# Schematic.net
KiCad netlist of a schematic drawn in Altium Designer
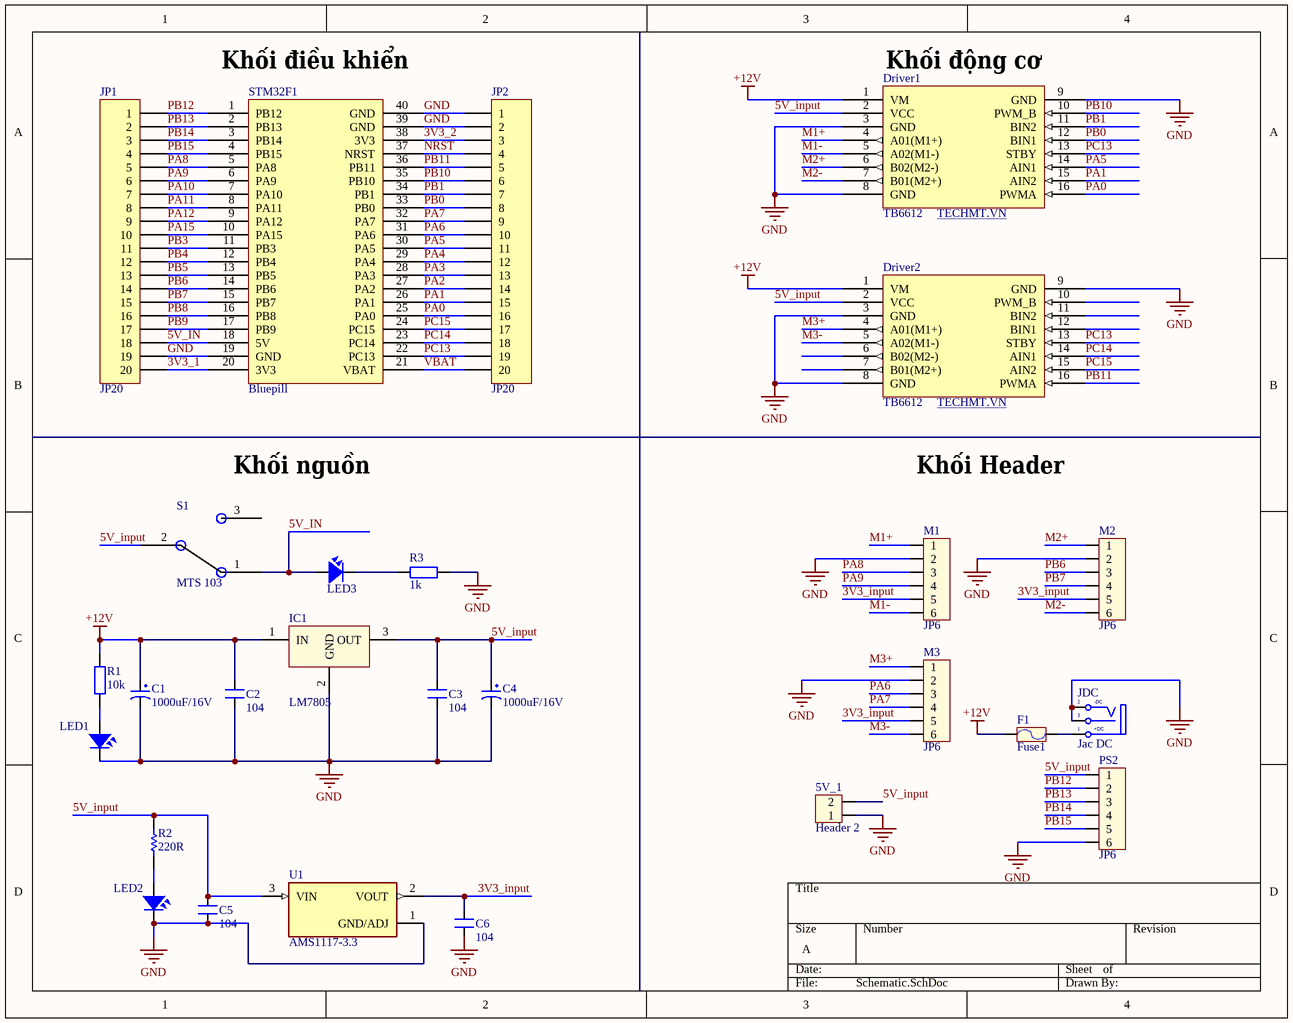
[diagram p0: Schematic.SchDoc]

(export (version "E")
  (design (tool "Eeschema 10.0.6"))
  (components
    (comp (ref "5V_1")
      (value "Header 2")
      (footprint "HED2")
      (description "Header 2 (Green)")
      (libsource (lib "echipkool-com-library") (part "Hed2"))
    )
    (comp (ref "C1")
      (value "1000uF/16V")
      (footprint "CP1.5/3.4")
      (description "Cap 100uF/35V - 470uF/16V")
      (libsource (lib "echipkool-com-library") (part "CP3"))
    )
    (comp (ref "C2")
      (value "104")
      (footprint "CN2")
      (description "Cap np 104 => 105pF")
      (libsource (lib "syhaunguyen") (part "CN2"))
    )
    (comp (ref "C3")
      (value "104")
      (footprint "CN2")
      (description "Cap np 104 => 105pF")
      (libsource (lib "syhaunguyen") (part "CN2"))
    )
    (comp (ref "C4")
      (value "1000uF/16V")
      (footprint "CP1.5/3.4")
      (description "Cap 100uF/35V - 470uF/16V")
      (libsource (lib "echipkool-com-library") (part "CP3"))
    )
    (comp (ref "C5")
      (value "104")
      (footprint "CN2")
      (description "Cap np 104 => 105pF")
      (libsource (lib "syhaunguyen") (part "CN2"))
    )
    (comp (ref "C6")
      (value "104")
      (footprint "CN2")
      (description "Cap np 104 => 105pF")
      (libsource (lib "echipkool-com-library") (part "CN2"))
    )
    (comp (ref "Driver1")
      (value "TB6612")
      (footprint "TB6612")
      (fields (field (name "WEB") "TECHMT.VN"))
      (libsource (lib "TechMT.VN_Lib_Project v2") (part "TB6612"))
    )
    (comp (ref "Driver2")
      (value "TB6612")
      (footprint "TB6612")
      (fields (field (name "WEB") "TECHMT.VN"))
      (libsource (lib "TechMT.VN_Lib_Project v2") (part "TB6612"))
    )
    (comp (ref "F1")
      (value "Fuse1")
      (footprint "Fuse1")
      (description "Fuse")
      (fields (field (name "DESIGNED BY") "VanDungEvn"))
      (libsource (lib "LIBRARYALT") (part "Fuse"))
    )
    (comp (ref "IC1")
      (value "LM7805")
      (footprint "QTO-220")
      (description "On ap +, from + 5 to + 24VDC")
      (libsource (lib "echipkool-com-library") (part "LM78xx"))
    )
    (comp (ref "JDC")
      (value "Jac DC")
      (footprint "DC-IN")
      (description "Jac DC input")
      (libsource (lib "syhaunguyen") (part "DCIN"))
    )
    (comp (ref "JP1")
      (value "JP20")
      (footprint "JP20-D1T")
      (description "WR-PHD 2.54 mm Angled Socket Header")
      (fields
        (field (name "MANUFACTURER") "Würth Elektronik eiSos GmbH")
        (field (name "PARTNO") "613020143121")
        (field (name "CREATED BY") "Karrer Zheng")
      )
      (libsource (lib "TechMT.VN_Lib_Project v2") (part "JP20"))
    )
    (comp (ref "JP2")
      (value "JP20")
      (footprint "JP20-D1T")
      (description "WR-PHD 2.54 mm Angled Socket Header")
      (fields
        (field (name "MANUFACTURER") "Würth Elektronik eiSos GmbH")
        (field (name "PARTNO") "613020143121")
        (field (name "CREATED BY") "Karrer Zheng")
      )
      (libsource (lib "") (part "JP20_1"))
    )
    (comp (ref "LED1")
      (value "LED")
      (footprint "LED-3")
      (description "LED Single colour Green and Red")
      (libsource (lib "echipkool-com-library") (part "LED"))
    )
    (comp (ref "LED2")
      (value "LED")
      (footprint "LED-3")
      (description "LED Single colour Green and Red")
      (libsource (lib "echipkool-com-library") (part "LED"))
    )
    (comp (ref "LED3")
      (value "LED")
      (footprint "LED-3")
      (description "LED Single colour Green and Red")
      (libsource (lib "echipkool-com-library") (part "LED"))
    )
    (comp (ref "M1")
      (value "JP6")
      (footprint "CON_6P")
      (description "Connector 6")
      (libsource (lib "My Library") (part "Con6"))
    )
    (comp (ref "M2")
      (value "JP6")
      (footprint "CON_6P")
      (description "Connector 6")
      (libsource (lib "echipkool-com-library") (part "Con6"))
    )
    (comp (ref "M3")
      (value "JP6")
      (footprint "CON_6P")
      (description "Connector 6")
      (libsource (lib "echipkool-com-library") (part "Con6"))
    )
    (comp (ref "PS2")
      (value "JP6")
      (footprint "CON_6P")
      (description "Connector 6")
      (libsource (lib "echipkool-com-library") (part "Con6"))
    )
    (comp (ref "R1")
      (value "10k")
      (footprint "R1/4W")
      (description "Resistor 1/4W")
      (libsource (lib "echipkool-com-library") (part "R1/4W"))
    )
    (comp (ref "R2")
      (value "220R")
      (footprint "R1/4W")
      (description "Resistor")
      (fields
        (field (name "MANUFACTURER") "Generic Components")
        (field (name "Comment") "Res1")
        (field (name "PUBLISHER") "Altium Hobart Technology Centre")
      )
      (libsource (lib "echipkool-com-library") (part "Res1_4"))
    )
    (comp (ref "R3")
      (value "1k")
      (footprint "R1/4W")
      (description "Resistor 1/4W")
      (libsource (lib "echipkool-com-library") (part "R1/4W"))
    )
    (comp (ref "S1") (value "MTS 103") (footprint "MTS 103") (libsource (lib "MTS103") (part "MTS 103")))
    (comp (ref "STM32F1")
      (value "Bluepill")
      (footprint "Blue Pill")
      (description "STM32F103C8T6")
      (libsource (lib "Bluepill") (part "STM32F103C8T6"))
    )
    (comp (ref "U1")
      (value "AMS1117-3.3")
      (footprint "SOT229P700X180-4N")
      (description "Sot223/Pkg 1-Amp 3.3-Volt Low Drop Out Voltage Regulatator")
      (fields (field (name "MF") "Advanced Monolithic Systems"))
      (libsource (lib "AMS1117-3.3") (part "AMS1117-3.3"))
    )
  )
  (nets
    (net (code "1") (name "+12V") (class "Default")
      (node (ref "C1") (pin "1") (pinfunction "1_1") (pintype "passive"))
      (node (ref "C2") (pin "2") (pinfunction "2_2") (pintype "passive"))
      (node (ref "Driver1") (pin "1") (pinfunction "VM_1") (pintype "power_in"))
      (node (ref "Driver2") (pin "1") (pinfunction "VM_1") (pintype "power_in"))
      (node (ref "F1") (pin "1") (pinfunction "1_1") (pintype "passive"))
      (node (ref "IC1") (pin "1") (pinfunction "IN_1") (pintype "passive"))
      (node (ref "R1") (pin "2") (pinfunction "2_2") (pintype "passive"))
    )
    (net (code "2") (name "/3V3_1") (class "Default")
      (node (ref "JP1") (pin "20") (pinfunction "20_20") (pintype "passive"))
      (node (ref "STM32F1") (pin "20") (pinfunction "3V3_20") (pintype "passive"))
    )
    (net (code "3") (name "/3V3_2") (class "Default")
      (node (ref "JP2") (pin "3") (pinfunction "3_3") (pintype "passive"))
      (node (ref "STM32F1") (pin "38") (pinfunction "3V3_38") (pintype "passive"))
    )
    (net (code "4") (name "/3V3_input") (class "Default")
      (node (ref "C6") (pin "2") (pinfunction "2_2") (pintype "passive"))
      (node (ref "M1") (pin "5") (pinfunction "5_5") (pintype "passive"))
      (node (ref "M2") (pin "5") (pinfunction "5_5") (pintype "passive"))
      (node (ref "M3") (pin "5") (pinfunction "5_5") (pintype "passive"))
      (node (ref "U1") (pin "2") (pinfunction "VOUT_2") (pintype "output"))
    )
    (net (code "5") (name "/5V_IN") (class "Default")
      (node (ref "JP1") (pin "18") (pinfunction "18_18") (pintype "passive"))
      (node (ref "LED3") (pin "1") (pinfunction "1_1") (pintype "passive"))
      (node (ref "S1") (pin "1") (pinfunction "1_1") (pintype "passive"))
      (node (ref "STM32F1") (pin "18") (pinfunction "5V_18") (pintype "passive"))
    )
    (net (code "6") (name "/5V_input") (class "Default")
      (node (ref "5V_1") (pin "2") (pinfunction "2_2") (pintype "passive"))
      (node (ref "C3") (pin "2") (pinfunction "2_2") (pintype "passive"))
      (node (ref "C4") (pin "1") (pinfunction "1_1") (pintype "passive"))
      (node (ref "C5") (pin "2") (pinfunction "2_2") (pintype "passive"))
      (node (ref "Driver1") (pin "2") (pinfunction "VCC_2") (pintype "power_in"))
      (node (ref "Driver2") (pin "2") (pinfunction "VCC_2") (pintype "power_in"))
      (node (ref "IC1") (pin "3") (pinfunction "OUT_3") (pintype "passive"))
      (node (ref "PS2") (pin "1") (pinfunction "1_1") (pintype "passive"))
      (node (ref "R2") (pin "2") (pinfunction "2_2") (pintype "passive"))
      (node (ref "S1") (pin "2") (pinfunction "4_2") (pintype "passive"))
      (node (ref "U1") (pin "3") (pinfunction "VIN_3") (pintype "input"))
    )
    (net (code "7") (name "/M1+") (class "Default")
      (node (ref "Driver1") (pin "4") (pinfunction "A01(M1+)_4") (pintype "output"))
      (node (ref "M1") (pin "1") (pinfunction "1_1") (pintype "passive"))
    )
    (net (code "8") (name "/M1-") (class "Default")
      (node (ref "Driver1") (pin "5") (pinfunction "A02(M1-)_5") (pintype "output"))
      (node (ref "M1") (pin "6") (pinfunction "6_6") (pintype "passive"))
    )
    (net (code "9") (name "/M2+") (class "Default")
      (node (ref "Driver1") (pin "6") (pinfunction "B02(M2-)_6") (pintype "output"))
      (node (ref "M2") (pin "1") (pinfunction "1_1") (pintype "passive"))
    )
    (net (code "10") (name "/M2-") (class "Default")
      (node (ref "Driver1") (pin "7") (pinfunction "B01(M2+)_7") (pintype "output"))
      (node (ref "M2") (pin "6") (pinfunction "6_6") (pintype "passive"))
    )
    (net (code "11") (name "/M3+") (class "Default")
      (node (ref "Driver2") (pin "4") (pinfunction "A01(M1+)_4") (pintype "output"))
      (node (ref "M3") (pin "1") (pinfunction "1_1") (pintype "passive"))
    )
    (net (code "12") (name "/M3-") (class "Default")
      (node (ref "Driver2") (pin "5") (pinfunction "A02(M1-)_5") (pintype "output"))
      (node (ref "M3") (pin "6") (pinfunction "6_6") (pintype "passive"))
    )
    (net (code "13") (name "/NRST") (class "Default")
      (node (ref "JP2") (pin "4") (pinfunction "4_4") (pintype "passive"))
      (node (ref "STM32F1") (pin "37") (pinfunction "NRST_37") (pintype "passive"))
    )
    (net (code "14") (name "/PA0") (class "Default")
      (node (ref "Driver1") (pin "16") (pinfunction "PWMA_16") (pintype "input"))
      (node (ref "JP2") (pin "16") (pinfunction "16_16") (pintype "passive"))
      (node (ref "STM32F1") (pin "25") (pinfunction "PA0_25") (pintype "passive"))
    )
    (net (code "15") (name "/PA1") (class "Default")
      (node (ref "Driver1") (pin "15") (pinfunction "AIN2_15") (pintype "input"))
      (node (ref "JP2") (pin "15") (pinfunction "15_15") (pintype "passive"))
      (node (ref "STM32F1") (pin "26") (pinfunction "PA1_26") (pintype "passive"))
    )
    (net (code "16") (name "/PA2") (class "Default")
      (node (ref "JP2") (pin "14") (pinfunction "14_14") (pintype "passive"))
      (node (ref "STM32F1") (pin "27") (pinfunction "PA2_27") (pintype "passive"))
    )
    (net (code "17") (name "/PA3") (class "Default")
      (node (ref "JP2") (pin "13") (pinfunction "13_13") (pintype "passive"))
      (node (ref "STM32F1") (pin "28") (pinfunction "PA3_28") (pintype "passive"))
    )
    (net (code "18") (name "/PA4") (class "Default")
      (node (ref "JP2") (pin "12") (pinfunction "12_12") (pintype "passive"))
      (node (ref "STM32F1") (pin "29") (pinfunction "PA4_29") (pintype "passive"))
    )
    (net (code "19") (name "/PA5") (class "Default")
      (node (ref "Driver1") (pin "14") (pinfunction "AIN1_14") (pintype "input"))
      (node (ref "JP2") (pin "11") (pinfunction "11_11") (pintype "passive"))
      (node (ref "STM32F1") (pin "30") (pinfunction "PA5_30") (pintype "passive"))
    )
    (net (code "20") (name "/PA6") (class "Default")
      (node (ref "JP2") (pin "10") (pinfunction "10_10") (pintype "passive"))
      (node (ref "M3") (pin "3") (pinfunction "3_3") (pintype "passive"))
      (node (ref "STM32F1") (pin "31") (pinfunction "PA6_31") (pintype "passive"))
    )
    (net (code "21") (name "/PA7") (class "Default")
      (node (ref "JP2") (pin "9") (pinfunction "9_9") (pintype "passive"))
      (node (ref "M3") (pin "4") (pinfunction "4_4") (pintype "passive"))
      (node (ref "STM32F1") (pin "32") (pinfunction "PA7_32") (pintype "passive"))
    )
    (net (code "22") (name "/PA8") (class "Default")
      (node (ref "JP1") (pin "5") (pinfunction "5_5") (pintype "passive"))
      (node (ref "M1") (pin "3") (pinfunction "3_3") (pintype "passive"))
      (node (ref "STM32F1") (pin "5") (pinfunction "PA8_5") (pintype "passive"))
    )
    (net (code "23") (name "/PA9") (class "Default")
      (node (ref "JP1") (pin "6") (pinfunction "6_6") (pintype "passive"))
      (node (ref "M1") (pin "4") (pinfunction "4_4") (pintype "passive"))
      (node (ref "STM32F1") (pin "6") (pinfunction "PA9_6") (pintype "passive"))
    )
    (net (code "24") (name "/PA10") (class "Default")
      (node (ref "JP1") (pin "7") (pinfunction "7_7") (pintype "passive"))
      (node (ref "STM32F1") (pin "7") (pinfunction "PA10_7") (pintype "passive"))
    )
    (net (code "25") (name "/PA11") (class "Default")
      (node (ref "JP1") (pin "8") (pinfunction "8_8") (pintype "passive"))
      (node (ref "STM32F1") (pin "8") (pinfunction "PA11_8") (pintype "passive"))
    )
    (net (code "26") (name "/PA12") (class "Default")
      (node (ref "JP1") (pin "9") (pinfunction "9_9") (pintype "passive"))
      (node (ref "STM32F1") (pin "9") (pinfunction "PA12_9") (pintype "passive"))
    )
    (net (code "27") (name "/PA15") (class "Default")
      (node (ref "JP1") (pin "10") (pinfunction "10_10") (pintype "passive"))
      (node (ref "STM32F1") (pin "10") (pinfunction "PA15_10") (pintype "passive"))
    )
    (net (code "28") (name "/PB0") (class "Default")
      (node (ref "Driver1") (pin "12") (pinfunction "BIN1_12") (pintype "input"))
      (node (ref "JP2") (pin "8") (pinfunction "8_8") (pintype "passive"))
      (node (ref "STM32F1") (pin "33") (pinfunction "PB0_33") (pintype "passive"))
    )
    (net (code "29") (name "/PB1") (class "Default")
      (node (ref "Driver1") (pin "11") (pinfunction "BIN2_11") (pintype "input"))
      (node (ref "JP2") (pin "7") (pinfunction "7_7") (pintype "passive"))
      (node (ref "STM32F1") (pin "34") (pinfunction "PB1_34") (pintype "passive"))
    )
    (net (code "30") (name "/PB3") (class "Default")
      (node (ref "JP1") (pin "11") (pinfunction "11_11") (pintype "passive"))
      (node (ref "STM32F1") (pin "11") (pinfunction "PB3_11") (pintype "passive"))
    )
    (net (code "31") (name "/PB4") (class "Default")
      (node (ref "JP1") (pin "12") (pinfunction "12_12") (pintype "passive"))
      (node (ref "STM32F1") (pin "12") (pinfunction "PB4_12") (pintype "passive"))
    )
    (net (code "32") (name "/PB5") (class "Default")
      (node (ref "JP1") (pin "13") (pinfunction "13_13") (pintype "passive"))
      (node (ref "STM32F1") (pin "13") (pinfunction "PB5_13") (pintype "passive"))
    )
    (net (code "33") (name "/PB6") (class "Default")
      (node (ref "JP1") (pin "14") (pinfunction "14_14") (pintype "passive"))
      (node (ref "M2") (pin "3") (pinfunction "3_3") (pintype "passive"))
      (node (ref "STM32F1") (pin "14") (pinfunction "PB6_14") (pintype "passive"))
    )
    (net (code "34") (name "/PB7") (class "Default")
      (node (ref "JP1") (pin "15") (pinfunction "15_15") (pintype "passive"))
      (node (ref "M2") (pin "4") (pinfunction "4_4") (pintype "passive"))
      (node (ref "STM32F1") (pin "15") (pinfunction "PB7_15") (pintype "passive"))
    )
    (net (code "35") (name "/PB8") (class "Default")
      (node (ref "JP1") (pin "16") (pinfunction "16_16") (pintype "passive"))
      (node (ref "STM32F1") (pin "16") (pinfunction "PB8_16") (pintype "passive"))
    )
    (net (code "36") (name "/PB9") (class "Default")
      (node (ref "JP1") (pin "17") (pinfunction "17_17") (pintype "passive"))
      (node (ref "STM32F1") (pin "17") (pinfunction "PB9_17") (pintype "passive"))
    )
    (net (code "37") (name "/PB10") (class "Default")
      (node (ref "Driver1") (pin "10") (pinfunction "PWM_B_10") (pintype "input"))
      (node (ref "JP2") (pin "6") (pinfunction "6_6") (pintype "passive"))
      (node (ref "STM32F1") (pin "35") (pinfunction "PB10_35") (pintype "passive"))
    )
    (net (code "38") (name "/PB11") (class "Default")
      (node (ref "Driver2") (pin "16") (pinfunction "PWMA_16") (pintype "input"))
      (node (ref "JP2") (pin "5") (pinfunction "5_5") (pintype "passive"))
      (node (ref "STM32F1") (pin "36") (pinfunction "PB11_36") (pintype "passive"))
    )
    (net (code "39") (name "/PB12") (class "Default")
      (node (ref "JP1") (pin "1") (pinfunction "1_1") (pintype "passive"))
      (node (ref "PS2") (pin "2") (pinfunction "2_2") (pintype "passive"))
      (node (ref "STM32F1") (pin "1") (pinfunction "PB12_1") (pintype "passive"))
    )
    (net (code "40") (name "/PB13") (class "Default")
      (node (ref "JP1") (pin "2") (pinfunction "2_2") (pintype "passive"))
      (node (ref "PS2") (pin "3") (pinfunction "3_3") (pintype "passive"))
      (node (ref "STM32F1") (pin "2") (pinfunction "PB13_2") (pintype "passive"))
    )
    (net (code "41") (name "/PB14") (class "Default")
      (node (ref "JP1") (pin "3") (pinfunction "3_3") (pintype "passive"))
      (node (ref "PS2") (pin "4") (pinfunction "4_4") (pintype "passive"))
      (node (ref "STM32F1") (pin "3") (pinfunction "PB14_3") (pintype "passive"))
    )
    (net (code "42") (name "/PB15") (class "Default")
      (node (ref "JP1") (pin "4") (pinfunction "4_4") (pintype "passive"))
      (node (ref "PS2") (pin "5") (pinfunction "5_5") (pintype "passive"))
      (node (ref "STM32F1") (pin "4") (pinfunction "PB15_4") (pintype "passive"))
    )
    (net (code "43") (name "/PC13") (class "Default")
      (node (ref "Driver1") (pin "13") (pinfunction "STBY_13") (pintype "input"))
      (node (ref "Driver2") (pin "13") (pinfunction "STBY_13") (pintype "input"))
      (node (ref "JP2") (pin "19") (pinfunction "19_19") (pintype "passive"))
      (node (ref "STM32F1") (pin "22") (pinfunction "PC13_22") (pintype "passive"))
    )
    (net (code "44") (name "/PC14") (class "Default")
      (node (ref "Driver2") (pin "14") (pinfunction "AIN1_14") (pintype "input"))
      (node (ref "JP2") (pin "18") (pinfunction "18_18") (pintype "passive"))
      (node (ref "STM32F1") (pin "23") (pinfunction "PC14_23") (pintype "passive"))
    )
    (net (code "45") (name "/PC15") (class "Default")
      (node (ref "Driver2") (pin "15") (pinfunction "AIN2_15") (pintype "input"))
      (node (ref "JP2") (pin "17") (pinfunction "17_17") (pintype "passive"))
      (node (ref "STM32F1") (pin "24") (pinfunction "PC15_24") (pintype "passive"))
    )
    (net (code "46") (name "/VBAT") (class "Default")
      (node (ref "JP2") (pin "20") (pinfunction "20_20") (pintype "passive"))
      (node (ref "STM32F1") (pin "21") (pinfunction "VBAT_21") (pintype "passive"))
    )
    (net (code "47") (name "GND") (class "Default")
      (node (ref "5V_1") (pin "1") (pinfunction "1_1") (pintype "passive"))
      (node (ref "C1") (pin "2") (pinfunction "2_2") (pintype "passive"))
      (node (ref "C2") (pin "1") (pinfunction "1_1") (pintype "passive"))
      (node (ref "C3") (pin "1") (pinfunction "1_1") (pintype "passive"))
      (node (ref "C4") (pin "2") (pinfunction "2_2") (pintype "passive"))
      (node (ref "C5") (pin "1") (pinfunction "1_1") (pintype "passive"))
      (node (ref "C6") (pin "1") (pinfunction "1_1") (pintype "passive"))
      (node (ref "Driver1") (pin "3") (pinfunction "GND_3") (pintype "power_in"))
      (node (ref "Driver1") (pin "8") (pinfunction "GND_8") (pintype "power_in"))
      (node (ref "Driver1") (pin "9") (pinfunction "GND_9") (pintype "power_in"))
      (node (ref "Driver2") (pin "3") (pinfunction "GND_3") (pintype "power_in"))
      (node (ref "Driver2") (pin "8") (pinfunction "GND_8") (pintype "power_in"))
      (node (ref "Driver2") (pin "9") (pinfunction "GND_9") (pintype "power_in"))
      (node (ref "IC1") (pin "2") (pinfunction "GND_2") (pintype "passive"))
      (node (ref "JDC") (pin "2") (pinfunction "TN_2") (pintype "passive"))
      (node (ref "JDC") (pin "3") (pinfunction "S_3") (pintype "power_in"))
      (node (ref "JP1") (pin "19") (pinfunction "19_19") (pintype "passive"))
      (node (ref "JP2") (pin "1") (pinfunction "1_1") (pintype "passive"))
      (node (ref "JP2") (pin "2") (pinfunction "2_2") (pintype "passive"))
      (node (ref "LED1") (pin "2") (pinfunction "2_2") (pintype "passive"))
      (node (ref "LED2") (pin "2") (pinfunction "2_2") (pintype "passive"))
      (node (ref "M1") (pin "2") (pinfunction "2_2") (pintype "passive"))
      (node (ref "M2") (pin "2") (pinfunction "2_2") (pintype "passive"))
      (node (ref "M3") (pin "2") (pinfunction "2_2") (pintype "passive"))
      (node (ref "PS2") (pin "6") (pinfunction "6_6") (pintype "passive"))
      (node (ref "R3") (pin "2") (pinfunction "2_2") (pintype "passive"))
      (node (ref "STM32F1") (pin "19") (pinfunction "GND_19") (pintype "passive"))
      (node (ref "STM32F1") (pin "39") (pinfunction "GND_39") (pintype "passive"))
      (node (ref "STM32F1") (pin "40") (pinfunction "GND_40") (pintype "passive"))
      (node (ref "U1") (pin "1") (pinfunction "GND/ADJ_1") (pintype "power_in"))
    )
    (net (code "48") (name "Net-(JDC-T)") (class "Default")
      (node (ref "F1") (pin "2") (pinfunction "2_2") (pintype "passive"))
      (node (ref "JDC") (pin "1") (pinfunction "T_1") (pintype "passive"))
    )
    (net (code "49") (name "Net-(LED1-Pad1)") (class "Default")
      (node (ref "LED1") (pin "1") (pinfunction "1_1") (pintype "passive"))
      (node (ref "R1") (pin "1") (pinfunction "1_1") (pintype "passive"))
    )
    (net (code "50") (name "Net-(LED2-Pad1)") (class "Default")
      (node (ref "LED2") (pin "1") (pinfunction "1_1") (pintype "passive"))
      (node (ref "R2") (pin "1") (pinfunction "1_1") (pintype "passive"))
    )
    (net (code "51") (name "Net-(LED3-Pad2)") (class "Default")
      (node (ref "LED3") (pin "2") (pinfunction "2_2") (pintype "passive"))
      (node (ref "R3") (pin "1") (pinfunction "1_1") (pintype "passive"))
    )
    (net (code "52") (name "unconnected-(Driver2-B01(M2+)-Pad7)") (class "Default")
      (node (ref "Driver2") (pin "7") (pinfunction "B01(M2+)_7") (pintype "output"))
    )
    (net (code "53") (name "unconnected-(Driver2-B02(M2-)-Pad6)") (class "Default")
      (node (ref "Driver2") (pin "6") (pinfunction "B02(M2-)_6") (pintype "output"))
    )
    (net (code "54") (name "unconnected-(Driver2-BIN1-Pad12)") (class "Default")
      (node (ref "Driver2") (pin "12") (pinfunction "BIN1_12") (pintype "input"))
    )
    (net (code "55") (name "unconnected-(Driver2-BIN2-Pad11)") (class "Default")
      (node (ref "Driver2") (pin "11") (pinfunction "BIN2_11") (pintype "input"))
    )
    (net (code "56") (name "unconnected-(Driver2-PWM_B-Pad10)") (class "Default")
      (node (ref "Driver2") (pin "10") (pinfunction "PWM_B_10") (pintype "input"))
    )
    (net (code "57") (name "unconnected-(S1-5-Pad3)") (class "Default")
      (node (ref "S1") (pin "3") (pinfunction "5_3") (pintype "passive"))
    )
  )
)
